# Cargador_RasPi3HAT_CamSlot_v2_0.net
KiCad netlist of a schematic drawn in EAGLE
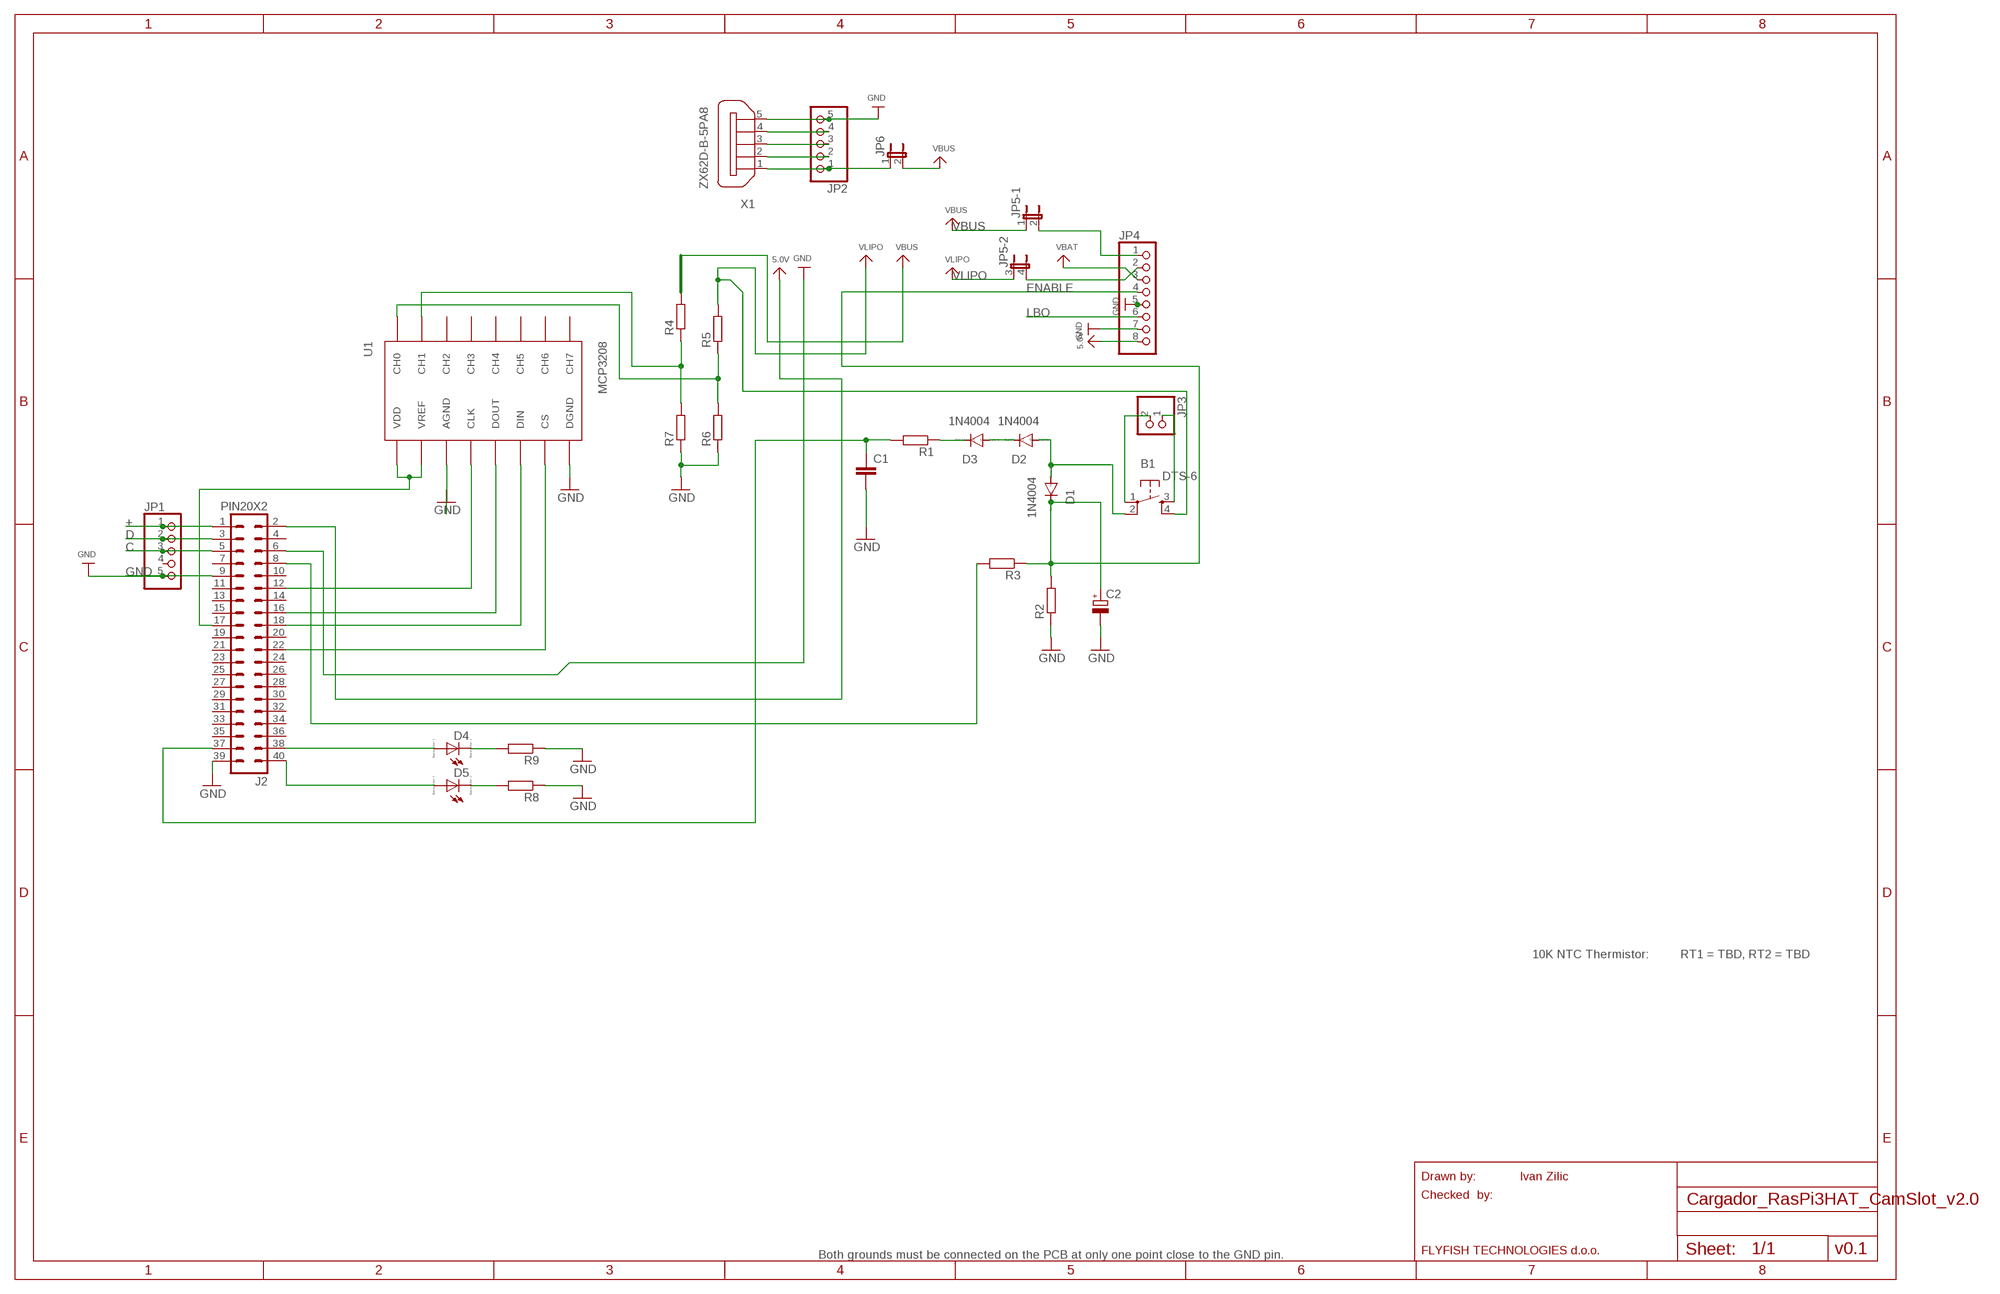
[diagram p0: schematic, sheet 1]

(export (version "E")
  (design (tool "Eeschema 10.0.6"))
  (components
    (comp (ref "B1")
      (value "DTS-6")
      (footprint "eagle-import:DTS-6")
      (libsource (lib "eagle-import") (part "DTS-6"))
    )
    (comp (ref "C1")
      (value "C2.5/2")
      (footprint "eagle-import:C2.5-2")
      (libsource (lib "eagle-import") (part "C2.5/2"))
    )
    (comp (ref "C2")
      (value "CPOL-EUE5-4")
      (footprint "eagle-import:E5-4")
      (libsource (lib "eagle-import") (part "CPOL-EUE5-4"))
    )
    (comp (ref "D1")
      (value "1N4004")
      (footprint "eagle-import:DO41-10")
      (libsource (lib "eagle-import") (part "1N4004"))
    )
    (comp (ref "D2")
      (value "1N4004")
      (footprint "eagle-import:DO41-10")
      (libsource (lib "eagle-import") (part "1N4004"))
    )
    (comp (ref "D3")
      (value "1N4004")
      (footprint "eagle-import:DO41-10")
      (libsource (lib "eagle-import") (part "1N4004"))
    )
    (comp (ref "D4")
      (value "LED_ELD260")
      (footprint "eagle-import:LED_LD260")
      (libsource (lib "eagle-import") (part "LED_ELD260"))
    )
    (comp (ref "D5")
      (value "LED_ELD260")
      (footprint "eagle-import:LED_LD260")
      (libsource (lib "eagle-import") (part "LED_ELD260"))
    )
    (comp (ref "J2")
      (value "PIN20X2")
      (footprint "eagle-import:PIN_20X2")
      (libsource (lib "eagle-import") (part "PIN20X2"))
    )
    (comp (ref "JP1")
      (value "PINHD-1X5")
      (footprint "eagle-import:1X05")
      (libsource (lib "eagle-import") (part "PINHD-1X5"))
    )
    (comp (ref "JP2")
      (value "PINHD-1X5")
      (footprint "eagle-import:1X05")
      (libsource (lib "eagle-import") (part "PINHD-1X5"))
    )
    (comp (ref "JP3")
      (value "PINHD-1X2")
      (footprint "eagle-import:1X02")
      (libsource (lib "eagle-import") (part "PINHD-1X2"))
    )
    (comp (ref "JP4")
      (value "HEADER-1X8")
      (footprint "eagle-import:1X08_OVAL")
      (libsource (lib "eagle-import") (part "HEADER-1X8"))
    )
    (comp (ref "JP5")
      (value "JP2QE")
      (footprint "eagle-import:JP2Q")
      (libsource (lib "eagle-import") (part "JP2QE"))
    )
    (comp (ref "JP6")
      (value "JP1E")
      (footprint "eagle-import:JP1")
      (libsource (lib "eagle-import") (part "JP1E"))
    )
    (comp (ref "R1")
      (value "R-EU_0207/10")
      (footprint "eagle-import:0207_10")
      (libsource (lib "eagle-import") (part "R-EU_0207/10"))
    )
    (comp (ref "R2")
      (value "R-EU_0207/10")
      (footprint "eagle-import:0207_10")
      (libsource (lib "eagle-import") (part "R-EU_0207/10"))
    )
    (comp (ref "R3")
      (value "R-EU_0207/10")
      (footprint "eagle-import:0207_10")
      (libsource (lib "eagle-import") (part "R-EU_0207/10"))
    )
    (comp (ref "R4")
      (value "R-EU_0207/10")
      (footprint "eagle-import:0207_10")
      (libsource (lib "eagle-import") (part "R-EU_0207/10"))
    )
    (comp (ref "R5")
      (value "R-EU_0207/10")
      (footprint "eagle-import:0207_10")
      (libsource (lib "eagle-import") (part "R-EU_0207/10"))
    )
    (comp (ref "R6")
      (value "R-EU_0207/10")
      (footprint "eagle-import:0207_10")
      (libsource (lib "eagle-import") (part "R-EU_0207/10"))
    )
    (comp (ref "R7")
      (value "R-EU_0207/10")
      (footprint "eagle-import:0207_10")
      (libsource (lib "eagle-import") (part "R-EU_0207/10"))
    )
    (comp (ref "R8")
      (value "R-EU_0207/10")
      (footprint "eagle-import:0207_10")
      (libsource (lib "eagle-import") (part "R-EU_0207/10"))
    )
    (comp (ref "R9")
      (value "R-EU_0207/10")
      (footprint "eagle-import:0207_10")
      (libsource (lib "eagle-import") (part "R-EU_0207/10"))
    )
    (comp (ref "U1")
      (value "MCP3208")
      (footprint "eagle-import:DIL16")
      (libsource (lib "eagle-import") (part "MCP3208"))
    )
    (comp (ref "X1")
      (value "ZX62D-B-5PA8")
      (footprint "eagle-import:ZX62D-B-5PA8")
      (fields (field (name "MF") "Hirose"))
      (libsource (lib "eagle-import") (part "ZX62D-B-5PA8"))
    )
  )
  (nets
    (net (code "1") (name "/+") (class "Default")
      (node (ref "J2") (pin "1") (pinfunction "1_1") (pintype "passive"))
      (node (ref "JP1") (pin "1") (pinfunction "1_1") (pintype "passive"))
    )
    (net (code "2") (name "/C") (class "Default")
      (node (ref "J2") (pin "5") (pinfunction "5_5") (pintype "passive"))
      (node (ref "JP1") (pin "3") (pinfunction "3_3") (pintype "passive"))
    )
    (net (code "3") (name "/D") (class "Default")
      (node (ref "J2") (pin "3") (pinfunction "3_3") (pintype "passive"))
      (node (ref "JP1") (pin "2") (pinfunction "2_2") (pintype "passive"))
    )
    (net (code "4") (name "/ENABLE") (class "Default")
      (node (ref "C2") (pin "+") (pinfunction "+_+") (pintype "passive"))
      (node (ref "D1") (pin "C") (pinfunction "C_C") (pintype "passive"))
      (node (ref "JP4") (pin "4") (pinfunction "4_4") (pintype "passive"))
      (node (ref "R2") (pin "2") (pinfunction "2_2") (pintype "passive"))
      (node (ref "R3") (pin "1") (pinfunction "1_1") (pintype "passive"))
    )
    (net (code "5") (name "/LBO") (class "Default")
      (node (ref "JP4") (pin "6") (pinfunction "6_6") (pintype "passive"))
    )
    (net (code "6") (name "5.0V") (class "Default")
      (node (ref "J2") (pin "2") (pinfunction "2_2") (pintype "passive"))
      (node (ref "JP4") (pin "8") (pinfunction "8_8") (pintype "passive"))
    )
    (net (code "7") (name "GND") (class "Default")
      (node (ref "C1") (pin "2") (pinfunction "2_2") (pintype "passive"))
      (node (ref "C2") (pin "-") (pinfunction "-_-") (pintype "passive"))
      (node (ref "J2") (pin "39") (pinfunction "39_39") (pintype "passive"))
      (node (ref "J2") (pin "6") (pinfunction "6_6") (pintype "passive"))
      (node (ref "J2") (pin "9") (pinfunction "9_9") (pintype "passive"))
      (node (ref "JP1") (pin "5") (pinfunction "5_5") (pintype "passive"))
      (node (ref "JP2") (pin "5") (pinfunction "5_5") (pintype "passive"))
      (node (ref "JP4") (pin "5") (pinfunction "5_5") (pintype "passive"))
      (node (ref "JP4") (pin "7") (pinfunction "7_7") (pintype "passive"))
      (node (ref "R2") (pin "1") (pinfunction "1_1") (pintype "passive"))
      (node (ref "R6") (pin "1") (pinfunction "1_1") (pintype "passive"))
      (node (ref "R7") (pin "1") (pinfunction "1_1") (pintype "passive"))
      (node (ref "R8") (pin "1") (pinfunction "1_1") (pintype "passive"))
      (node (ref "R9") (pin "1") (pinfunction "1_1") (pintype "passive"))
      (node (ref "U1") (pin "AGND") (pinfunction "AGND_AGND") (pintype "power_in"))
      (node (ref "U1") (pin "DGND") (pinfunction "DGND_DGND") (pintype "power_in"))
      (node (ref "X1") (pin "5") (pinfunction "5_5") (pintype "passive"))
    )
    (net (code "8") (name "Net-(B1-Pad1)") (class "Default")
      (node (ref "B1") (pin "1") (pinfunction "1_1") (pintype "passive"))
      (node (ref "JP3") (pin "2") (pinfunction "2_2") (pintype "passive"))
    )
    (net (code "9") (name "Net-(B1-Pad2)") (class "Default")
      (node (ref "B1") (pin "2") (pinfunction "2_2") (pintype "passive"))
      (node (ref "D1") (pin "A") (pinfunction "A_A") (pintype "passive"))
      (node (ref "D2") (pin "A") (pinfunction "A_A") (pintype "passive"))
    )
    (net (code "10") (name "Net-(B1-Pad3)") (class "Default")
      (node (ref "B1") (pin "3") (pinfunction "3_3") (pintype "passive"))
      (node (ref "JP3") (pin "1") (pinfunction "1_1") (pintype "passive"))
    )
    (net (code "11") (name "Net-(C1-Pad1)") (class "Default")
      (node (ref "C1") (pin "1") (pinfunction "1_1") (pintype "passive"))
      (node (ref "J2") (pin "37") (pinfunction "37_37") (pintype "passive"))
      (node (ref "R1") (pin "2") (pinfunction "2_2") (pintype "passive"))
    )
    (net (code "12") (name "Net-(D2-PadC)") (class "Default")
      (node (ref "D2") (pin "C") (pinfunction "C_C") (pintype "passive"))
      (node (ref "D3") (pin "A") (pinfunction "A_A") (pintype "passive"))
    )
    (net (code "13") (name "Net-(D3-PadC)") (class "Default")
      (node (ref "D3") (pin "C") (pinfunction "C_C") (pintype "passive"))
      (node (ref "R1") (pin "1") (pinfunction "1_1") (pintype "passive"))
    )
    (net (code "14") (name "Net-(D4-C)") (class "Default")
      (node (ref "D4") (pin "K") (pinfunction "C_K") (pintype "passive"))
      (node (ref "R9") (pin "2") (pinfunction "2_2") (pintype "passive"))
    )
    (net (code "15") (name "Net-(D4-PadA)") (class "Default")
      (node (ref "D4") (pin "A") (pinfunction "A_A") (pintype "passive"))
      (node (ref "J2") (pin "38") (pinfunction "38_38") (pintype "passive"))
    )
    (net (code "16") (name "Net-(D5-C)") (class "Default")
      (node (ref "D5") (pin "K") (pinfunction "C_K") (pintype "passive"))
      (node (ref "R8") (pin "2") (pinfunction "2_2") (pintype "passive"))
    )
    (net (code "17") (name "Net-(D5-PadA)") (class "Default")
      (node (ref "D5") (pin "A") (pinfunction "A_A") (pintype "passive"))
      (node (ref "J2") (pin "40") (pinfunction "40_40") (pintype "passive"))
    )
    (net (code "18") (name "Net-(J2-Pad8)") (class "Default")
      (node (ref "J2") (pin "8") (pinfunction "8_8") (pintype "passive"))
      (node (ref "R3") (pin "2") (pinfunction "2_2") (pintype "passive"))
    )
    (net (code "19") (name "Net-(J2-Pad12)") (class "Default")
      (node (ref "J2") (pin "12") (pinfunction "12_12") (pintype "passive"))
      (node (ref "U1") (pin "CLK") (pinfunction "CLK_CLK") (pintype "input"))
    )
    (net (code "20") (name "Net-(J2-Pad16)") (class "Default")
      (node (ref "J2") (pin "16") (pinfunction "16_16") (pintype "passive"))
      (node (ref "U1") (pin "DOUT") (pinfunction "DOUT_DOUT") (pintype "output"))
    )
    (net (code "21") (name "Net-(J2-Pad17)") (class "Default")
      (node (ref "J2") (pin "17") (pinfunction "17_17") (pintype "passive"))
      (node (ref "U1") (pin "VDD") (pinfunction "VDD_VDD") (pintype "power_in"))
      (node (ref "U1") (pin "VREF") (pinfunction "VREF_VREF") (pintype "input"))
    )
    (net (code "22") (name "Net-(J2-Pad18)") (class "Default")
      (node (ref "J2") (pin "18") (pinfunction "18_18") (pintype "passive"))
      (node (ref "U1") (pin "DIN") (pinfunction "DIN_DIN") (pintype "input"))
    )
    (net (code "23") (name "Net-(J2-Pad22)") (class "Default")
      (node (ref "J2") (pin "22") (pinfunction "22_22") (pintype "passive"))
      (node (ref "U1") (pin "CS") (pinfunction "CS_CS") (pintype "input"))
    )
    (net (code "24") (name "Net-(JP2-Pad1)") (class "Default")
      (node (ref "JP2") (pin "1") (pinfunction "1_1") (pintype "passive"))
      (node (ref "JP6") (pin "1") (pinfunction "1_1") (pintype "passive"))
      (node (ref "X1") (pin "1") (pinfunction "1_1") (pintype "passive"))
    )
    (net (code "25") (name "Net-(JP2-Pad2)") (class "Default")
      (node (ref "JP2") (pin "2") (pinfunction "2_2") (pintype "passive"))
      (node (ref "X1") (pin "2") (pinfunction "2_2") (pintype "passive"))
    )
    (net (code "26") (name "Net-(JP2-Pad3)") (class "Default")
      (node (ref "JP2") (pin "3") (pinfunction "3_3") (pintype "passive"))
      (node (ref "X1") (pin "3") (pinfunction "3_3") (pintype "passive"))
    )
    (net (code "27") (name "Net-(JP2-Pad4)") (class "Default")
      (node (ref "JP2") (pin "4") (pinfunction "4_4") (pintype "passive"))
      (node (ref "X1") (pin "4") (pinfunction "4_4") (pintype "passive"))
    )
    (net (code "28") (name "Net-(R4-Pad1)") (class "Default")
      (node (ref "R4") (pin "1") (pinfunction "1_1") (pintype "passive"))
      (node (ref "R7") (pin "2") (pinfunction "2_2") (pintype "passive"))
      (node (ref "U1") (pin "CH1") (pinfunction "CH1_CH1") (pintype "input"))
    )
    (net (code "29") (name "Net-(R5-Pad1)") (class "Default")
      (node (ref "R5") (pin "1") (pinfunction "1_1") (pintype "passive"))
      (node (ref "R6") (pin "2") (pinfunction "2_2") (pintype "passive"))
      (node (ref "U1") (pin "CH0") (pinfunction "CH0_CH0") (pintype "input"))
    )
    (net (code "30") (name "VBAT") (class "Default")
      (node (ref "JP4") (pin "3") (pinfunction "3_3") (pintype "passive"))
    )
    (net (code "31") (name "VBUS") (class "Default")
      (node (ref "JP4") (pin "1") (pinfunction "1_1") (pintype "passive"))
      (node (ref "JP5") (pin "1") (pinfunction "1_1") (pintype "passive"))
      (node (ref "JP5") (pin "2") (pinfunction "2_2") (pintype "passive"))
      (node (ref "JP6") (pin "2") (pinfunction "2_2") (pintype "passive"))
      (node (ref "R4") (pin "2") (pinfunction "2_2") (pintype "passive"))
    )
    (net (code "32") (name "VLIPO") (class "Default")
      (node (ref "B1") (pin "4") (pinfunction "4_4") (pintype "passive"))
      (node (ref "JP4") (pin "2") (pinfunction "2_2") (pintype "passive"))
      (node (ref "JP5") (pin "3") (pinfunction "1_3") (pintype "passive"))
      (node (ref "JP5") (pin "4") (pinfunction "2_4") (pintype "passive"))
      (node (ref "R5") (pin "2") (pinfunction "2_2") (pintype "passive"))
    )
    (net (code "33") (name "unconnected-(J2-Pad4)") (class "Default")
      (node (ref "J2") (pin "4") (pinfunction "4_4") (pintype "passive"))
    )
    (net (code "34") (name "unconnected-(J2-Pad7)") (class "Default")
      (node (ref "J2") (pin "7") (pinfunction "7_7") (pintype "passive"))
    )
    (net (code "35") (name "unconnected-(J2-Pad10)") (class "Default")
      (node (ref "J2") (pin "10") (pinfunction "10_10") (pintype "passive"))
    )
    (net (code "36") (name "unconnected-(J2-Pad11)") (class "Default")
      (node (ref "J2") (pin "11") (pinfunction "11_11") (pintype "passive"))
    )
    (net (code "37") (name "unconnected-(J2-Pad13)") (class "Default")
      (node (ref "J2") (pin "13") (pinfunction "13_13") (pintype "passive"))
    )
    (net (code "38") (name "unconnected-(J2-Pad14)") (class "Default")
      (node (ref "J2") (pin "14") (pinfunction "14_14") (pintype "passive"))
    )
    (net (code "39") (name "unconnected-(J2-Pad15)") (class "Default")
      (node (ref "J2") (pin "15") (pinfunction "15_15") (pintype "passive"))
    )
    (net (code "40") (name "unconnected-(J2-Pad19)") (class "Default")
      (node (ref "J2") (pin "19") (pinfunction "19_19") (pintype "passive"))
    )
    (net (code "41") (name "unconnected-(J2-Pad20)") (class "Default")
      (node (ref "J2") (pin "20") (pinfunction "20_20") (pintype "passive"))
    )
    (net (code "42") (name "unconnected-(J2-Pad21)") (class "Default")
      (node (ref "J2") (pin "21") (pinfunction "21_21") (pintype "passive"))
    )
    (net (code "43") (name "unconnected-(J2-Pad23)") (class "Default")
      (node (ref "J2") (pin "23") (pinfunction "23_23") (pintype "passive"))
    )
    (net (code "44") (name "unconnected-(J2-Pad24)") (class "Default")
      (node (ref "J2") (pin "24") (pinfunction "24_24") (pintype "passive"))
    )
    (net (code "45") (name "unconnected-(J2-Pad25)") (class "Default")
      (node (ref "J2") (pin "25") (pinfunction "25_25") (pintype "passive"))
    )
    (net (code "46") (name "unconnected-(J2-Pad26)") (class "Default")
      (node (ref "J2") (pin "26") (pinfunction "26_26") (pintype "passive"))
    )
    (net (code "47") (name "unconnected-(J2-Pad27)") (class "Default")
      (node (ref "J2") (pin "27") (pinfunction "27_27") (pintype "passive"))
    )
    (net (code "48") (name "unconnected-(J2-Pad28)") (class "Default")
      (node (ref "J2") (pin "28") (pinfunction "28_28") (pintype "passive"))
    )
    (net (code "49") (name "unconnected-(J2-Pad29)") (class "Default")
      (node (ref "J2") (pin "29") (pinfunction "29_29") (pintype "passive"))
    )
    (net (code "50") (name "unconnected-(J2-Pad30)") (class "Default")
      (node (ref "J2") (pin "30") (pinfunction "30_30") (pintype "passive"))
    )
    (net (code "51") (name "unconnected-(J2-Pad31)") (class "Default")
      (node (ref "J2") (pin "31") (pinfunction "31_31") (pintype "passive"))
    )
    (net (code "52") (name "unconnected-(J2-Pad32)") (class "Default")
      (node (ref "J2") (pin "32") (pinfunction "32_32") (pintype "passive"))
    )
    (net (code "53") (name "unconnected-(J2-Pad33)") (class "Default")
      (node (ref "J2") (pin "33") (pinfunction "33_33") (pintype "passive"))
    )
    (net (code "54") (name "unconnected-(J2-Pad34)") (class "Default")
      (node (ref "J2") (pin "34") (pinfunction "34_34") (pintype "passive"))
    )
    (net (code "55") (name "unconnected-(J2-Pad35)") (class "Default")
      (node (ref "J2") (pin "35") (pinfunction "35_35") (pintype "passive"))
    )
    (net (code "56") (name "unconnected-(J2-Pad36)") (class "Default")
      (node (ref "J2") (pin "36") (pinfunction "36_36") (pintype "passive"))
    )
    (net (code "57") (name "unconnected-(JP1-Pad4)") (class "Default")
      (node (ref "JP1") (pin "4") (pinfunction "4_4") (pintype "passive"))
    )
    (net (code "58") (name "unconnected-(U1-PadCH2)") (class "Default")
      (node (ref "U1") (pin "CH2") (pinfunction "CH2_CH2") (pintype "input"))
    )
    (net (code "59") (name "unconnected-(U1-PadCH3)") (class "Default")
      (node (ref "U1") (pin "CH3") (pinfunction "CH3_CH3") (pintype "input"))
    )
    (net (code "60") (name "unconnected-(U1-PadCH4)") (class "Default")
      (node (ref "U1") (pin "CH4") (pinfunction "CH4_CH4") (pintype "input"))
    )
    (net (code "61") (name "unconnected-(U1-PadCH5)") (class "Default")
      (node (ref "U1") (pin "CH5") (pinfunction "CH5_CH5") (pintype "input"))
    )
    (net (code "62") (name "unconnected-(U1-PadCH6)") (class "Default")
      (node (ref "U1") (pin "CH6") (pinfunction "CH6_CH6") (pintype "input"))
    )
    (net (code "63") (name "unconnected-(U1-PadCH7)") (class "Default")
      (node (ref "U1") (pin "CH7") (pinfunction "CH7_CH7") (pintype "input"))
    )
  )
)
